# switching.net
KiCad netlist of a schematic drawn in EAGLE
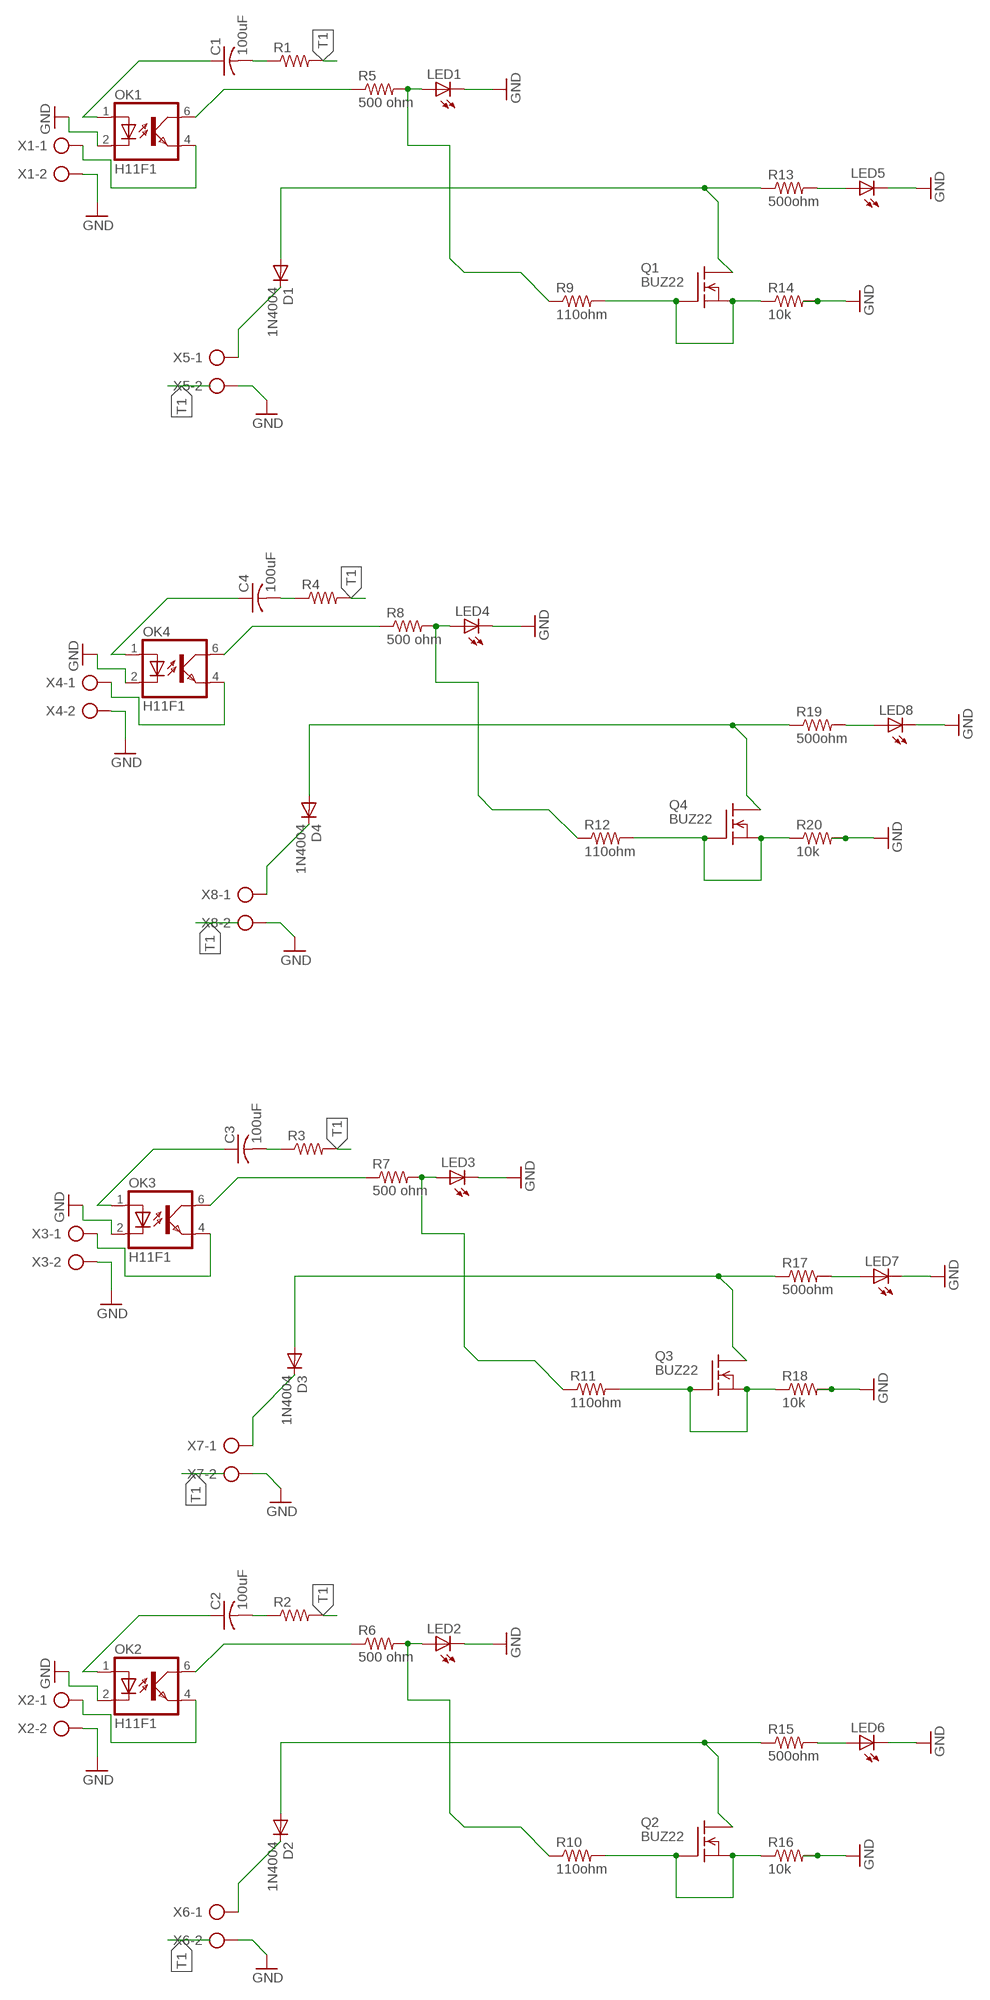
[diagram p0: schematic, sheet 1]

(export (version "E")
  (design (tool "Eeschema 10.0.6"))
  (components
    (comp (ref "C1")
      (value "100uF")
      (footprint "eagle-import:C025-024X044")
      (fields (field (name "MF") "AVX") (field (name "MPN") "08055C104KAT2A"))
      (libsource (lib "eagle-import") (part "C-US025-024X044"))
    )
    (comp (ref "C2")
      (value "100uF")
      (footprint "eagle-import:C025-024X044")
      (fields (field (name "MF") "AVX") (field (name "MPN") "08055C104KAT2A"))
      (libsource (lib "eagle-import") (part "C-US025-024X044"))
    )
    (comp (ref "C3")
      (value "100uF")
      (footprint "eagle-import:C025-024X044")
      (fields (field (name "MF") "AVX") (field (name "MPN") "08055C104KAT2A"))
      (libsource (lib "eagle-import") (part "C-US025-024X044"))
    )
    (comp (ref "C4")
      (value "100uF")
      (footprint "eagle-import:C025-024X044")
      (fields (field (name "MF") "AVX") (field (name "MPN") "08055C104KAT2A"))
      (libsource (lib "eagle-import") (part "C-US025-024X044"))
    )
    (comp (ref "D1")
      (value "1N4004")
      (footprint "eagle-import:DO41-10")
      (fields (field (name "MF") "ON SEMICONDUCTOR") (field (name "MPN") "1N4004G"))
      (libsource (lib "eagle-import") (part "1N4004"))
    )
    (comp (ref "D2")
      (value "1N4004")
      (footprint "eagle-import:DO41-10")
      (fields (field (name "MF") "ON SEMICONDUCTOR") (field (name "MPN") "1N4004G"))
      (libsource (lib "eagle-import") (part "1N4004"))
    )
    (comp (ref "D3")
      (value "1N4004")
      (footprint "eagle-import:DO41-10")
      (fields (field (name "MF") "ON SEMICONDUCTOR") (field (name "MPN") "1N4004G"))
      (libsource (lib "eagle-import") (part "1N4004"))
    )
    (comp (ref "D4")
      (value "1N4004")
      (footprint "eagle-import:DO41-10")
      (fields (field (name "MF") "ON SEMICONDUCTOR") (field (name "MPN") "1N4004G"))
      (libsource (lib "eagle-import") (part "1N4004"))
    )
    (comp (ref "LED1")
      (value "LED3MM")
      (footprint "eagle-import:LED3MM")
      (fields (field (name "MF") "LUMEX") (field (name "MPN") "SSL-LX3044LID."))
      (libsource (lib "eagle-import") (part "LED3MM"))
    )
    (comp (ref "LED2")
      (value "LED3MM")
      (footprint "eagle-import:LED3MM")
      (fields (field (name "MF") "LUMEX") (field (name "MPN") "SSL-LX3044LID."))
      (libsource (lib "eagle-import") (part "LED3MM"))
    )
    (comp (ref "LED3")
      (value "LED3MM")
      (footprint "eagle-import:LED3MM")
      (fields (field (name "MF") "LUMEX") (field (name "MPN") "SSL-LX3044LID."))
      (libsource (lib "eagle-import") (part "LED3MM"))
    )
    (comp (ref "LED4")
      (value "LED3MM")
      (footprint "eagle-import:LED3MM")
      (fields (field (name "MF") "LUMEX") (field (name "MPN") "SSL-LX3044LID."))
      (libsource (lib "eagle-import") (part "LED3MM"))
    )
    (comp (ref "LED5")
      (value "LED3MM")
      (footprint "eagle-import:LED3MM")
      (fields (field (name "MF") "LUMEX") (field (name "MPN") "SSL-LX3044LID."))
      (libsource (lib "eagle-import") (part "LED3MM"))
    )
    (comp (ref "LED6")
      (value "LED3MM")
      (footprint "eagle-import:LED3MM")
      (fields (field (name "MF") "LUMEX") (field (name "MPN") "SSL-LX3044LID."))
      (libsource (lib "eagle-import") (part "LED3MM"))
    )
    (comp (ref "LED7")
      (value "LED3MM")
      (footprint "eagle-import:LED3MM")
      (fields (field (name "MF") "LUMEX") (field (name "MPN") "SSL-LX3044LID."))
      (libsource (lib "eagle-import") (part "LED3MM"))
    )
    (comp (ref "LED8")
      (value "LED3MM")
      (footprint "eagle-import:LED3MM")
      (fields (field (name "MF") "LUMEX") (field (name "MPN") "SSL-LX3044LID."))
      (libsource (lib "eagle-import") (part "LED3MM"))
    )
    (comp (ref "OK1")
      (value "H11F1")
      (footprint "eagle-import:DIL05")
      (libsource (lib "eagle-import") (part "H11F1"))
    )
    (comp (ref "OK2")
      (value "H11F1")
      (footprint "eagle-import:DIL05")
      (libsource (lib "eagle-import") (part "H11F1"))
    )
    (comp (ref "OK3")
      (value "H11F1")
      (footprint "eagle-import:DIL05")
      (libsource (lib "eagle-import") (part "H11F1"))
    )
    (comp (ref "OK4")
      (value "H11F1")
      (footprint "eagle-import:DIL05")
      (libsource (lib "eagle-import") (part "H11F1"))
    )
    (comp (ref "Q1")
      (value "BUZ22")
      (footprint "eagle-import:TO220")
      (fields (field (name "MF") "INFINEON") (field (name "MPN") "IRF1310NPBF"))
      (libsource (lib "eagle-import") (part "BUZ22"))
    )
    (comp (ref "Q2")
      (value "BUZ22")
      (footprint "eagle-import:TO220")
      (fields (field (name "MF") "INFINEON") (field (name "MPN") "IRF1310NPBF"))
      (libsource (lib "eagle-import") (part "BUZ22"))
    )
    (comp (ref "Q3")
      (value "BUZ22")
      (footprint "eagle-import:TO220")
      (fields (field (name "MF") "INFINEON") (field (name "MPN") "IRF1310NPBF"))
      (libsource (lib "eagle-import") (part "BUZ22"))
    )
    (comp (ref "Q4")
      (value "BUZ22")
      (footprint "eagle-import:TO220")
      (fields (field (name "MF") "INFINEON") (field (name "MPN") "IRF1310NPBF"))
      (libsource (lib "eagle-import") (part "BUZ22"))
    )
    (comp (ref "R1")
      (value "R-US_0204/7")
      (footprint "eagle-import:0204_7")
      (fields (field (name "MF") "YAGEO (PHYCOMP)") (field (name "MPN") "CC0402KRX7R7BB104"))
      (libsource (lib "eagle-import") (part "R-US_0204/7"))
    )
    (comp (ref "R2")
      (value "R-US_0204/7")
      (footprint "eagle-import:0204_7")
      (fields (field (name "MF") "YAGEO (PHYCOMP)") (field (name "MPN") "CC0402KRX7R7BB104"))
      (libsource (lib "eagle-import") (part "R-US_0204/7"))
    )
    (comp (ref "R3")
      (value "R-US_0204/7")
      (footprint "eagle-import:0204_7")
      (fields (field (name "MF") "YAGEO (PHYCOMP)") (field (name "MPN") "CC0402KRX7R7BB104"))
      (libsource (lib "eagle-import") (part "R-US_0204/7"))
    )
    (comp (ref "R4")
      (value "R-US_0204/7")
      (footprint "eagle-import:0204_7")
      (fields (field (name "MF") "YAGEO (PHYCOMP)") (field (name "MPN") "CC0402KRX7R7BB104"))
      (libsource (lib "eagle-import") (part "R-US_0204/7"))
    )
    (comp (ref "R5")
      (value "500 ohm")
      (footprint "eagle-import:0204_7")
      (fields (field (name "MF") "YAGEO (PHYCOMP)") (field (name "MPN") "CC0402JRNPO9BN101"))
      (libsource (lib "eagle-import") (part "R-US_0204/7"))
    )
    (comp (ref "R6")
      (value "500 ohm")
      (footprint "eagle-import:0204_7")
      (fields (field (name "MF") "YAGEO (PHYCOMP)") (field (name "MPN") "CC0402JRNPO9BN101"))
      (libsource (lib "eagle-import") (part "R-US_0204/7"))
    )
    (comp (ref "R7")
      (value "500 ohm")
      (footprint "eagle-import:0204_7")
      (fields (field (name "MF") "YAGEO (PHYCOMP)") (field (name "MPN") "CC0402JRNPO9BN101"))
      (libsource (lib "eagle-import") (part "R-US_0204/7"))
    )
    (comp (ref "R8")
      (value "500 ohm")
      (footprint "eagle-import:0204_7")
      (fields (field (name "MF") "YAGEO (PHYCOMP)") (field (name "MPN") "CC0402JRNPO9BN101"))
      (libsource (lib "eagle-import") (part "R-US_0204/7"))
    )
    (comp (ref "R9")
      (value "110ohm")
      (footprint "eagle-import:0204_7")
      (fields (field (name "MF") "PANASONIC ELECTRONIC COMPONENTS") (field (name "MPN") "ERJ3GEYJ111V"))
      (libsource (lib "eagle-import") (part "R-US_0204/7"))
    )
    (comp (ref "R10")
      (value "110ohm")
      (footprint "eagle-import:0204_7")
      (fields (field (name "MF") "PANASONIC ELECTRONIC COMPONENTS") (field (name "MPN") "ERJ3GEYJ111V"))
      (libsource (lib "eagle-import") (part "R-US_0204/7"))
    )
    (comp (ref "R11")
      (value "110ohm")
      (footprint "eagle-import:0204_7")
      (fields (field (name "MF") "PANASONIC ELECTRONIC COMPONENTS") (field (name "MPN") "ERJ3GEYJ111V"))
      (libsource (lib "eagle-import") (part "R-US_0204/7"))
    )
    (comp (ref "R12")
      (value "110ohm")
      (footprint "eagle-import:0204_7")
      (fields (field (name "MF") "PANASONIC ELECTRONIC COMPONENTS") (field (name "MPN") "ERJ3GEYJ111V"))
      (libsource (lib "eagle-import") (part "R-US_0204/7"))
    )
    (comp (ref "R13")
      (value "500ohm")
      (footprint "eagle-import:0204_7")
      (fields (field (name "MF") "YAGEO (PHYCOMP)") (field (name "MPN") "CC0402JRNPO9BN101"))
      (libsource (lib "eagle-import") (part "R-US_0204/7"))
    )
    (comp (ref "R14")
      (value "10k")
      (footprint "eagle-import:0204_7")
      (fields (field (name "MF") "VISHAY") (field (name "MPN") "CRCW040210K0FKED"))
      (libsource (lib "eagle-import") (part "R-US_0204/7"))
    )
    (comp (ref "R15")
      (value "500ohm")
      (footprint "eagle-import:0204_7")
      (fields (field (name "MF") "YAGEO (PHYCOMP)") (field (name "MPN") "CC0402JRNPO9BN101"))
      (libsource (lib "eagle-import") (part "R-US_0204/7"))
    )
    (comp (ref "R16")
      (value "10k")
      (footprint "eagle-import:0204_7")
      (fields (field (name "MF") "VISHAY") (field (name "MPN") "CRCW040210K0FKED"))
      (libsource (lib "eagle-import") (part "R-US_0204/7"))
    )
    (comp (ref "R17")
      (value "500ohm")
      (footprint "eagle-import:0204_7")
      (fields (field (name "MF") "YAGEO (PHYCOMP)") (field (name "MPN") "CC0402JRNPO9BN101"))
      (libsource (lib "eagle-import") (part "R-US_0204/7"))
    )
    (comp (ref "R18")
      (value "10k")
      (footprint "eagle-import:0204_7")
      (fields (field (name "MF") "VISHAY") (field (name "MPN") "CRCW040210K0FKED"))
      (libsource (lib "eagle-import") (part "R-US_0204/7"))
    )
    (comp (ref "R19")
      (value "500ohm")
      (footprint "eagle-import:0204_7")
      (fields (field (name "MF") "YAGEO (PHYCOMP)") (field (name "MPN") "CC0402JRNPO9BN101"))
      (libsource (lib "eagle-import") (part "R-US_0204/7"))
    )
    (comp (ref "R20")
      (value "10k")
      (footprint "eagle-import:0204_7")
      (fields (field (name "MF") "VISHAY") (field (name "MPN") "CRCW040210K0FKED"))
      (libsource (lib "eagle-import") (part "R-US_0204/7"))
    )
    (comp (ref "X1")
      (value "AK500/2")
      (footprint "eagle-import:AK500_2")
      (libsource (lib "eagle-import") (part "AK500/2"))
    )
    (comp (ref "X2")
      (value "AK500/2")
      (footprint "eagle-import:AK500_2")
      (libsource (lib "eagle-import") (part "AK500/2"))
    )
    (comp (ref "X3")
      (value "AK500/2")
      (footprint "eagle-import:AK500_2")
      (libsource (lib "eagle-import") (part "AK500/2"))
    )
    (comp (ref "X4")
      (value "AK500/2")
      (footprint "eagle-import:AK500_2")
      (libsource (lib "eagle-import") (part "AK500/2"))
    )
    (comp (ref "X5")
      (value "AK500/2")
      (footprint "eagle-import:AK500_2")
      (libsource (lib "eagle-import") (part "AK500/2"))
    )
    (comp (ref "X6")
      (value "AK500/2")
      (footprint "eagle-import:AK500_2")
      (libsource (lib "eagle-import") (part "AK500/2"))
    )
    (comp (ref "X7")
      (value "AK500/2")
      (footprint "eagle-import:AK500_2")
      (libsource (lib "eagle-import") (part "AK500/2"))
    )
    (comp (ref "X8")
      (value "AK500/2")
      (footprint "eagle-import:AK500_2")
      (libsource (lib "eagle-import") (part "AK500/2"))
    )
  )
  (nets
    (net (code "1") (name "GND") (class "Default")
      (node (ref "LED1") (pin "K") (pinfunction "C_K") (pintype "passive"))
      (node (ref "LED2") (pin "K") (pinfunction "C_K") (pintype "passive"))
      (node (ref "LED3") (pin "K") (pinfunction "C_K") (pintype "passive"))
      (node (ref "LED4") (pin "K") (pinfunction "C_K") (pintype "passive"))
      (node (ref "LED5") (pin "K") (pinfunction "C_K") (pintype "passive"))
      (node (ref "LED6") (pin "K") (pinfunction "C_K") (pintype "passive"))
      (node (ref "LED7") (pin "K") (pinfunction "C_K") (pintype "passive"))
      (node (ref "LED8") (pin "K") (pinfunction "C_K") (pintype "passive"))
      (node (ref "OK1") (pin "2") (pinfunction "C_2") (pintype "passive"))
      (node (ref "OK2") (pin "2") (pinfunction "C_2") (pintype "passive"))
      (node (ref "OK3") (pin "2") (pinfunction "C_2") (pintype "passive"))
      (node (ref "OK4") (pin "2") (pinfunction "C_2") (pintype "passive"))
      (node (ref "R14") (pin "2") (pinfunction "2_2") (pintype "passive"))
      (node (ref "R16") (pin "2") (pinfunction "2_2") (pintype "passive"))
      (node (ref "R18") (pin "2") (pinfunction "2_2") (pintype "passive"))
      (node (ref "R20") (pin "2") (pinfunction "2_2") (pintype "passive"))
      (node (ref "X1") (pin "2") (pinfunction "KL_2") (pintype "passive"))
      (node (ref "X2") (pin "2") (pinfunction "KL_2") (pintype "passive"))
      (node (ref "X3") (pin "2") (pinfunction "KL_2") (pintype "passive"))
      (node (ref "X4") (pin "2") (pinfunction "KL_2") (pintype "passive"))
      (node (ref "X5") (pin "2") (pinfunction "KL_2") (pintype "passive"))
      (node (ref "X6") (pin "2") (pinfunction "KL_2") (pintype "passive"))
      (node (ref "X7") (pin "2") (pinfunction "KL_2") (pintype "passive"))
      (node (ref "X8") (pin "2") (pinfunction "KL_2") (pintype "passive"))
    )
    (net (code "2") (name "Net-(C1-Pad2)") (class "Default")
      (node (ref "C1") (pin "2") (pinfunction "2_2") (pintype "passive"))
      (node (ref "R1") (pin "1") (pinfunction "1_1") (pintype "passive"))
    )
    (net (code "3") (name "Net-(C2-Pad2)") (class "Default")
      (node (ref "C2") (pin "2") (pinfunction "2_2") (pintype "passive"))
      (node (ref "R2") (pin "1") (pinfunction "1_1") (pintype "passive"))
    )
    (net (code "4") (name "Net-(C3-Pad2)") (class "Default")
      (node (ref "C3") (pin "2") (pinfunction "2_2") (pintype "passive"))
      (node (ref "R3") (pin "1") (pinfunction "1_1") (pintype "passive"))
    )
    (net (code "5") (name "Net-(C4-Pad2)") (class "Default")
      (node (ref "C4") (pin "2") (pinfunction "2_2") (pintype "passive"))
      (node (ref "R4") (pin "1") (pinfunction "1_1") (pintype "passive"))
    )
    (net (code "6") (name "Net-(LED1-PadA)") (class "Default")
      (node (ref "LED1") (pin "A") (pinfunction "A_A") (pintype "passive"))
      (node (ref "R5") (pin "2") (pinfunction "2_2") (pintype "passive"))
      (node (ref "R9") (pin "1") (pinfunction "1_1") (pintype "passive"))
    )
    (net (code "7") (name "Net-(LED2-PadA)") (class "Default")
      (node (ref "LED2") (pin "A") (pinfunction "A_A") (pintype "passive"))
      (node (ref "R10") (pin "1") (pinfunction "1_1") (pintype "passive"))
      (node (ref "R6") (pin "2") (pinfunction "2_2") (pintype "passive"))
    )
    (net (code "8") (name "Net-(LED3-PadA)") (class "Default")
      (node (ref "LED3") (pin "A") (pinfunction "A_A") (pintype "passive"))
      (node (ref "R11") (pin "1") (pinfunction "1_1") (pintype "passive"))
      (node (ref "R7") (pin "2") (pinfunction "2_2") (pintype "passive"))
    )
    (net (code "9") (name "Net-(LED4-PadA)") (class "Default")
      (node (ref "LED4") (pin "A") (pinfunction "A_A") (pintype "passive"))
      (node (ref "R12") (pin "1") (pinfunction "1_1") (pintype "passive"))
      (node (ref "R8") (pin "2") (pinfunction "2_2") (pintype "passive"))
    )
    (net (code "10") (name "Net-(LED5-PadA)") (class "Default")
      (node (ref "LED5") (pin "A") (pinfunction "A_A") (pintype "passive"))
      (node (ref "R13") (pin "2") (pinfunction "2_2") (pintype "passive"))
    )
    (net (code "11") (name "Net-(LED6-PadA)") (class "Default")
      (node (ref "LED6") (pin "A") (pinfunction "A_A") (pintype "passive"))
      (node (ref "R15") (pin "2") (pinfunction "2_2") (pintype "passive"))
    )
    (net (code "12") (name "Net-(LED7-PadA)") (class "Default")
      (node (ref "LED7") (pin "A") (pinfunction "A_A") (pintype "passive"))
      (node (ref "R17") (pin "2") (pinfunction "2_2") (pintype "passive"))
    )
    (net (code "13") (name "Net-(LED8-PadA)") (class "Default")
      (node (ref "LED8") (pin "A") (pinfunction "A_A") (pintype "passive"))
      (node (ref "R19") (pin "2") (pinfunction "2_2") (pintype "passive"))
    )
    (net (code "14") (name "Net-(OK1-A)") (class "Default")
      (node (ref "C1") (pin "1") (pinfunction "1_1") (pintype "passive"))
      (node (ref "OK1") (pin "1") (pinfunction "A_1") (pintype "passive"))
    )
    (net (code "15") (name "Net-(OK1-COL)") (class "Default")
      (node (ref "OK1") (pin "6") (pinfunction "COL_6") (pintype "passive"))
      (node (ref "R5") (pin "1") (pinfunction "1_1") (pintype "passive"))
    )
    (net (code "16") (name "Net-(OK1-EMIT)") (class "Default")
      (node (ref "OK1") (pin "4") (pinfunction "EMIT_4") (pintype "passive"))
      (node (ref "X1") (pin "1") (pinfunction "KL_1") (pintype "passive"))
    )
    (net (code "17") (name "Net-(OK2-A)") (class "Default")
      (node (ref "C2") (pin "1") (pinfunction "1_1") (pintype "passive"))
      (node (ref "OK2") (pin "1") (pinfunction "A_1") (pintype "passive"))
    )
    (net (code "18") (name "Net-(OK2-COL)") (class "Default")
      (node (ref "OK2") (pin "6") (pinfunction "COL_6") (pintype "passive"))
      (node (ref "R6") (pin "1") (pinfunction "1_1") (pintype "passive"))
    )
    (net (code "19") (name "Net-(OK2-EMIT)") (class "Default")
      (node (ref "OK2") (pin "4") (pinfunction "EMIT_4") (pintype "passive"))
      (node (ref "X2") (pin "1") (pinfunction "KL_1") (pintype "passive"))
    )
    (net (code "20") (name "Net-(OK3-A)") (class "Default")
      (node (ref "C3") (pin "1") (pinfunction "1_1") (pintype "passive"))
      (node (ref "OK3") (pin "1") (pinfunction "A_1") (pintype "passive"))
    )
    (net (code "21") (name "Net-(OK3-COL)") (class "Default")
      (node (ref "OK3") (pin "6") (pinfunction "COL_6") (pintype "passive"))
      (node (ref "R7") (pin "1") (pinfunction "1_1") (pintype "passive"))
    )
    (net (code "22") (name "Net-(OK3-EMIT)") (class "Default")
      (node (ref "OK3") (pin "4") (pinfunction "EMIT_4") (pintype "passive"))
      (node (ref "X3") (pin "1") (pinfunction "KL_1") (pintype "passive"))
    )
    (net (code "23") (name "Net-(OK4-A)") (class "Default")
      (node (ref "C4") (pin "1") (pinfunction "1_1") (pintype "passive"))
      (node (ref "OK4") (pin "1") (pinfunction "A_1") (pintype "passive"))
    )
    (net (code "24") (name "Net-(OK4-COL)") (class "Default")
      (node (ref "OK4") (pin "6") (pinfunction "COL_6") (pintype "passive"))
      (node (ref "R8") (pin "1") (pinfunction "1_1") (pintype "passive"))
    )
    (net (code "25") (name "Net-(OK4-EMIT)") (class "Default")
      (node (ref "OK4") (pin "4") (pinfunction "EMIT_4") (pintype "passive"))
      (node (ref "X4") (pin "1") (pinfunction "KL_1") (pintype "passive"))
    )
    (net (code "26") (name "Net-(Q1-D)") (class "Default")
      (node (ref "D1") (pin "A") (pinfunction "A_A") (pintype "passive"))
      (node (ref "Q1") (pin "2") (pinfunction "D_2") (pintype "passive"))
      (node (ref "R13") (pin "1") (pinfunction "1_1") (pintype "passive"))
    )
    (net (code "27") (name "Net-(Q1-G)") (class "Default")
      (node (ref "Q1") (pin "1") (pinfunction "G_1") (pintype "passive"))
      (node (ref "Q1") (pin "3") (pinfunction "S_3") (pintype "passive"))
      (node (ref "R14") (pin "1") (pinfunction "1_1") (pintype "passive"))
      (node (ref "R9") (pin "2") (pinfunction "2_2") (pintype "passive"))
    )
    (net (code "28") (name "Net-(Q2-D)") (class "Default")
      (node (ref "D2") (pin "A") (pinfunction "A_A") (pintype "passive"))
      (node (ref "Q2") (pin "2") (pinfunction "D_2") (pintype "passive"))
      (node (ref "R15") (pin "1") (pinfunction "1_1") (pintype "passive"))
    )
    (net (code "29") (name "Net-(Q2-G)") (class "Default")
      (node (ref "Q2") (pin "1") (pinfunction "G_1") (pintype "passive"))
      (node (ref "Q2") (pin "3") (pinfunction "S_3") (pintype "passive"))
      (node (ref "R10") (pin "2") (pinfunction "2_2") (pintype "passive"))
      (node (ref "R16") (pin "1") (pinfunction "1_1") (pintype "passive"))
    )
    (net (code "30") (name "Net-(Q3-D)") (class "Default")
      (node (ref "D3") (pin "A") (pinfunction "A_A") (pintype "passive"))
      (node (ref "Q3") (pin "2") (pinfunction "D_2") (pintype "passive"))
      (node (ref "R17") (pin "1") (pinfunction "1_1") (pintype "passive"))
    )
    (net (code "31") (name "Net-(Q3-G)") (class "Default")
      (node (ref "Q3") (pin "1") (pinfunction "G_1") (pintype "passive"))
      (node (ref "Q3") (pin "3") (pinfunction "S_3") (pintype "passive"))
      (node (ref "R11") (pin "2") (pinfunction "2_2") (pintype "passive"))
      (node (ref "R18") (pin "1") (pinfunction "1_1") (pintype "passive"))
    )
    (net (code "32") (name "Net-(Q4-D)") (class "Default")
      (node (ref "D4") (pin "A") (pinfunction "A_A") (pintype "passive"))
      (node (ref "Q4") (pin "2") (pinfunction "D_2") (pintype "passive"))
      (node (ref "R19") (pin "1") (pinfunction "1_1") (pintype "passive"))
    )
    (net (code "33") (name "Net-(Q4-G)") (class "Default")
      (node (ref "Q4") (pin "1") (pinfunction "G_1") (pintype "passive"))
      (node (ref "Q4") (pin "3") (pinfunction "S_3") (pintype "passive"))
      (node (ref "R12") (pin "2") (pinfunction "2_2") (pintype "passive"))
      (node (ref "R20") (pin "1") (pinfunction "1_1") (pintype "passive"))
    )
    (net (code "34") (name "Net-(X5A-KL)") (class "Default")
      (node (ref "D1") (pin "C") (pinfunction "C_C") (pintype "passive"))
      (node (ref "X5") (pin "1") (pinfunction "KL_1") (pintype "passive"))
    )
    (net (code "35") (name "Net-(X6A-KL)") (class "Default")
      (node (ref "D2") (pin "C") (pinfunction "C_C") (pintype "passive"))
      (node (ref "X6") (pin "1") (pinfunction "KL_1") (pintype "passive"))
    )
    (net (code "36") (name "Net-(X7A-KL)") (class "Default")
      (node (ref "D3") (pin "C") (pinfunction "C_C") (pintype "passive"))
      (node (ref "X7") (pin "1") (pinfunction "KL_1") (pintype "passive"))
    )
    (net (code "37") (name "Net-(X8A-KL)") (class "Default")
      (node (ref "D4") (pin "C") (pinfunction "C_C") (pintype "passive"))
      (node (ref "X8") (pin "1") (pinfunction "KL_1") (pintype "passive"))
    )
    (net (code "38") (name "T1") (class "Default")
      (node (ref "R1") (pin "2") (pinfunction "2_2") (pintype "passive"))
      (node (ref "R2") (pin "2") (pinfunction "2_2") (pintype "passive"))
      (node (ref "R3") (pin "2") (pinfunction "2_2") (pintype "passive"))
      (node (ref "R4") (pin "2") (pinfunction "2_2") (pintype "passive"))
    )
  )
)
